# 1004.net
KiCad netlist of a schematic drawn in Altium Designer
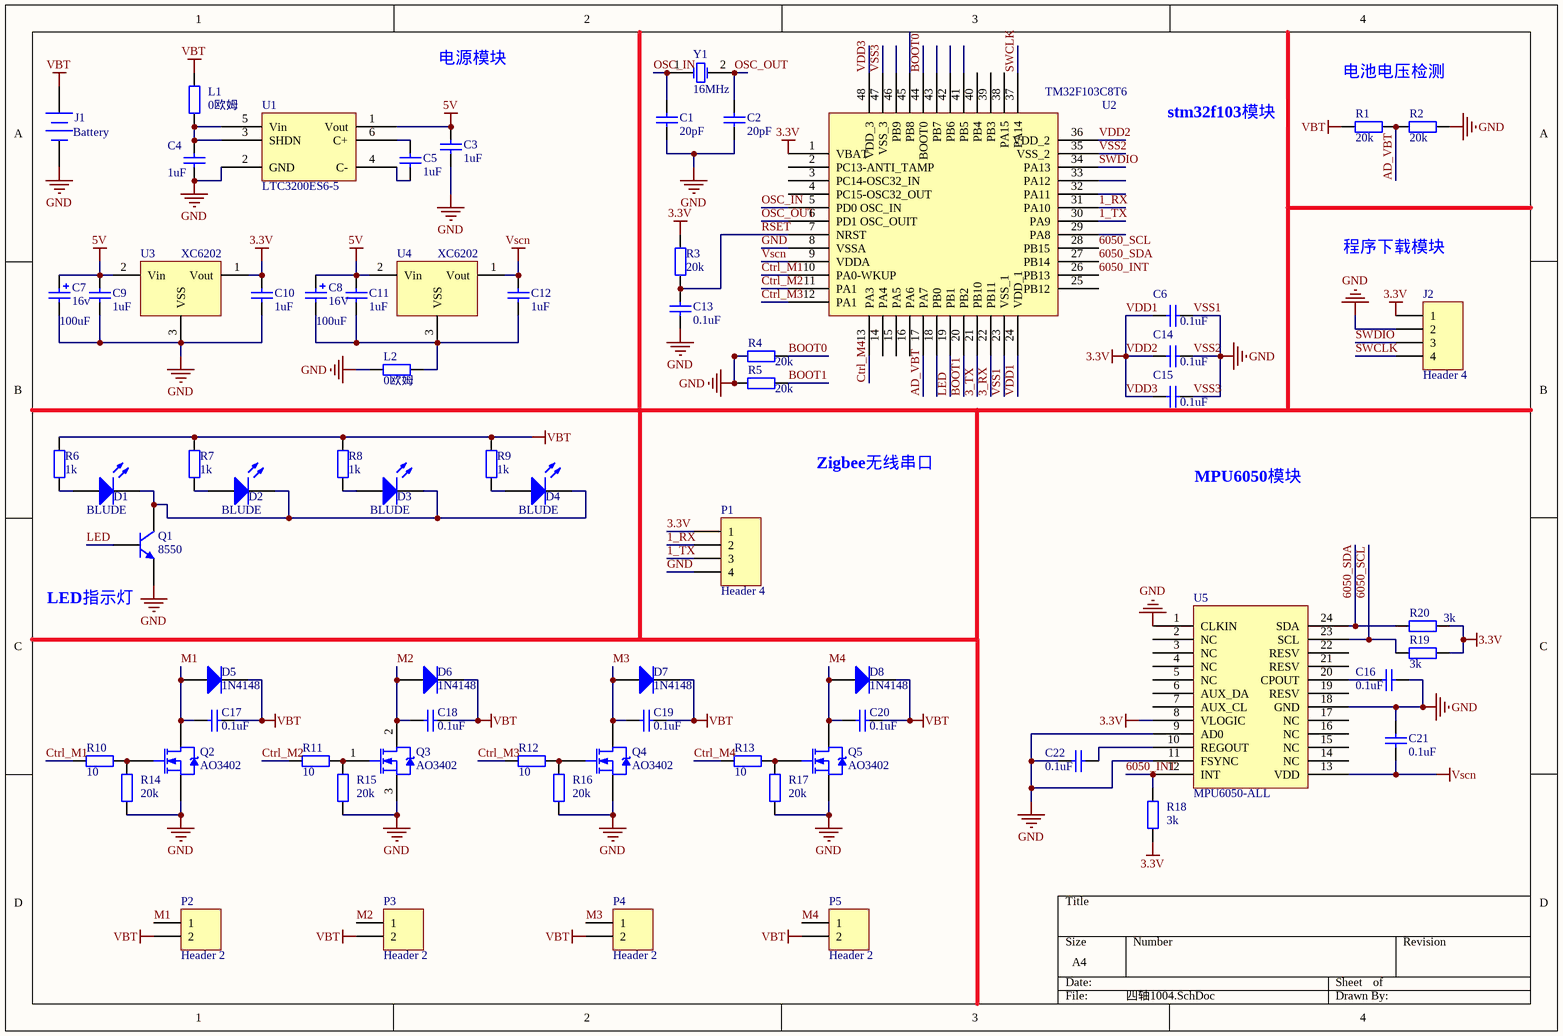
[diagram p0: 四轴1004.SchDoc]

(export (version "E")
  (design (tool "Eeschema 10.0.6"))
  (components
    (comp (ref "C1")
      (value "20pF")
      (footprint "J1-0603")
      (description "Capacitor")
      (fields (field (name "Comment") "Cap") (field (name "PUBLISHER") "Altium Limited"))
      (libsource (lib "Miscellaneous Devices") (part "Cap"))
    )
    (comp (ref "C2")
      (value "20pF")
      (footprint "J1-0603")
      (description "Capacitor")
      (fields (field (name "Comment") "Cap") (field (name "PUBLISHER") "Altium Limited"))
      (libsource (lib "Miscellaneous Devices") (part "Cap"))
    )
    (comp (ref "C3")
      (value "1uF")
      (footprint "J1-0603")
      (description "Capacitor")
      (fields (field (name "Comment") "Cap") (field (name "PUBLISHER") "Altium Limited"))
      (libsource (lib "Miscellaneous Devices") (part "Cap"))
    )
    (comp (ref "C4")
      (value "1uF")
      (footprint "J1-0603")
      (description "Capacitor")
      (fields (field (name "Comment") "Cap") (field (name "PUBLISHER") "Altium Limited"))
      (libsource (lib "Miscellaneous Devices") (part "Cap"))
    )
    (comp (ref "C5")
      (value "1uF")
      (footprint "J1-0603")
      (description "Capacitor")
      (fields (field (name "Comment") "Cap") (field (name "PUBLISHER") "Altium Limited"))
      (libsource (lib "Miscellaneous Devices") (part "Cap"))
    )
    (comp (ref "C6")
      (value "0.1uF")
      (footprint "J1-0603")
      (description "Capacitor")
      (fields (field (name "Comment") "Cap") (field (name "PUBLISHER") "Altium Limited"))
      (libsource (lib "Miscellaneous Devices") (part "Cap"))
    )
    (comp (ref "C7")
      (value "16v")
      (footprint "6032")
      (description "Polarized Capacitor (Axial)")
      (fields (field (name "ALTIUM_VALUE") "100uF") (field (name "PUBLISHER") "Altium Limited"))
      (libsource (lib "Miscellaneous Devices") (part "Cap Pol2"))
    )
    (comp (ref "C8")
      (value "16V")
      (footprint "6032")
      (description "Polarized Capacitor (Axial)")
      (fields (field (name "ALTIUM_VALUE") "100uF") (field (name "PUBLISHER") "Altium Limited"))
      (libsource (lib "Miscellaneous Devices") (part "Cap Pol2"))
    )
    (comp (ref "C9")
      (value "1uF")
      (footprint "J1-0603")
      (description "Capacitor")
      (fields (field (name "Comment") "Cap") (field (name "PUBLISHER") "Altium Limited"))
      (libsource (lib "Miscellaneous Devices") (part "Cap"))
    )
    (comp (ref "C10")
      (value "1uF")
      (footprint "J1-0603")
      (description "Capacitor")
      (fields (field (name "Comment") "Cap") (field (name "PUBLISHER") "Altium Limited"))
      (libsource (lib "Miscellaneous Devices") (part "Cap"))
    )
    (comp (ref "C11")
      (value "1uF")
      (footprint "J1-0603")
      (description "Capacitor")
      (fields (field (name "Comment") "Cap") (field (name "PUBLISHER") "Altium Limited"))
      (libsource (lib "Miscellaneous Devices") (part "Cap"))
    )
    (comp (ref "C12")
      (value "1uF")
      (footprint "J1-0603")
      (description "Capacitor")
      (fields (field (name "Comment") "Cap") (field (name "PUBLISHER") "Altium Limited"))
      (libsource (lib "Miscellaneous Devices") (part "Cap"))
    )
    (comp (ref "C13")
      (value "0.1uF")
      (footprint "J1-0603")
      (description "Capacitor")
      (fields (field (name "Comment") "Cap") (field (name "PUBLISHER") "Altium Limited"))
      (libsource (lib "Miscellaneous Devices") (part "Cap"))
    )
    (comp (ref "C14")
      (value "0.1uF")
      (footprint "J1-0603")
      (description "Capacitor")
      (fields (field (name "Comment") "Cap") (field (name "PUBLISHER") "Altium Limited"))
      (libsource (lib "Miscellaneous Devices") (part "Cap"))
    )
    (comp (ref "C15")
      (value "0.1uF")
      (footprint "J1-0603")
      (description "Capacitor")
      (fields (field (name "Comment") "Cap") (field (name "PUBLISHER") "Altium Limited"))
      (libsource (lib "Miscellaneous Devices") (part "Cap"))
    )
    (comp (ref "C16")
      (value "0.1uF")
      (footprint "J1-0603")
      (description "Capacitor")
      (fields (field (name "Comment") "Cap") (field (name "PUBLISHER") "Altium Limited"))
      (libsource (lib "Miscellaneous Devices") (part "Cap"))
    )
    (comp (ref "C17")
      (value "0.1uF")
      (footprint "J1-0603")
      (description "Capacitor")
      (fields (field (name "Comment") "Cap") (field (name "PUBLISHER") "Altium Limited"))
      (libsource (lib "Miscellaneous Devices") (part "Cap"))
    )
    (comp (ref "C18")
      (value "0.1uF")
      (footprint "J1-0603")
      (description "Capacitor")
      (fields (field (name "Comment") "Cap") (field (name "PUBLISHER") "Altium Limited"))
      (libsource (lib "Miscellaneous Devices") (part "Cap"))
    )
    (comp (ref "C19")
      (value "0.1uF")
      (footprint "J1-0603")
      (description "Capacitor")
      (fields (field (name "Comment") "Cap") (field (name "PUBLISHER") "Altium Limited"))
      (libsource (lib "Miscellaneous Devices") (part "Cap"))
    )
    (comp (ref "C20")
      (value "0.1uF")
      (footprint "J1-0603")
      (description "Capacitor")
      (fields (field (name "Comment") "Cap") (field (name "PUBLISHER") "Altium Limited"))
      (libsource (lib "Miscellaneous Devices") (part "Cap"))
    )
    (comp (ref "C21")
      (value "0.1uF")
      (footprint "J1-0603")
      (description "Capacitor")
      (fields (field (name "Comment") "Cap") (field (name "PUBLISHER") "Altium Limited"))
      (libsource (lib "Miscellaneous Devices") (part "Cap"))
    )
    (comp (ref "C22")
      (value "0.1uF")
      (footprint "J1-0603")
      (description "Capacitor")
      (fields (field (name "Comment") "Cap") (field (name "PUBLISHER") "Altium Limited"))
      (libsource (lib "Miscellaneous Devices") (part "Cap"))
    )
    (comp (ref "D1")
      (value "BLUDE")
      (footprint "J1-0603")
      (description "Typical INFRARED GaAs LED")
      (fields (field (name "PUBLISHER") "Altium Limited"))
      (libsource (lib "Miscellaneous Devices") (part "LED0"))
    )
    (comp (ref "D2")
      (value "BLUDE")
      (footprint "J1-0603")
      (description "Typical INFRARED GaAs LED")
      (fields (field (name "PUBLISHER") "Altium Limited"))
      (libsource (lib "Miscellaneous Devices") (part "LED0"))
    )
    (comp (ref "D3")
      (value "BLUDE")
      (footprint "J1-0603")
      (description "Typical INFRARED GaAs LED")
      (fields (field (name "PUBLISHER") "Altium Limited"))
      (libsource (lib "Miscellaneous Devices") (part "LED0"))
    )
    (comp (ref "D4")
      (value "BLUDE")
      (footprint "J1-0603")
      (description "Typical INFRARED GaAs LED")
      (fields (field (name "PUBLISHER") "Altium Limited"))
      (libsource (lib "Miscellaneous Devices") (part "LED0"))
    )
    (comp (ref "D5")
      (value "1N4148")
      (footprint "1206")
      (description "High Conductance Fast Diode")
      (fields (field (name "PUBLISHER") "Altium Limited"))
      (libsource (lib "Miscellaneous Devices") (part "Diode 1N4148"))
    )
    (comp (ref "D6")
      (value "1N4148")
      (footprint "1206")
      (description "High Conductance Fast Diode")
      (fields (field (name "PUBLISHER") "Altium Limited"))
      (libsource (lib "Miscellaneous Devices") (part "Diode 1N4148"))
    )
    (comp (ref "D7")
      (value "1N4148")
      (footprint "1206")
      (description "High Conductance Fast Diode")
      (fields (field (name "PUBLISHER") "Altium Limited"))
      (libsource (lib "Miscellaneous Devices") (part "Diode 1N4148"))
    )
    (comp (ref "D8")
      (value "1N4148")
      (footprint "1206")
      (description "High Conductance Fast Diode")
      (fields (field (name "PUBLISHER") "Altium Limited"))
      (libsource (lib "Miscellaneous Devices") (part "Diode 1N4148"))
    )
    (comp (ref "J1")
      (value "Battery")
      (footprint "DIP2-5.08")
      (description "Multicell Battery")
      (fields (field (name "PUBLISHER") "Altium Limited"))
      (libsource (lib "Miscellaneous Devices") (part "Battery"))
    )
    (comp (ref "J2")
      (value "Header 4")
      (footprint "HDR1X4")
      (description "Header, 4-Pin")
      (fields (field (name "PUBLISHER") "Altium Limited"))
      (libsource (lib "Miscellaneous Connectors") (part "Header 4"))
    )
    (comp (ref "L1")
      (value "0欧姆")
      (footprint "0805-1")
      (description "贴片电阻")
      (fields (field (name "Comment") "Res1") (field (name "PUBLISHER") "Altium Limited"))
      (libsource (lib "") (part "Res1_1"))
    )
    (comp (ref "L2")
      (value "0欧姆")
      (footprint "0805-1")
      (description "贴片电阻")
      (fields (field (name "Comment") "Res1") (field (name "PUBLISHER") "Altium Limited"))
      (libsource (lib "cell_1") (part "Res1"))
    )
    (comp (ref "P1")
      (value "Header 4")
      (footprint "HDR1X4")
      (description "Header, 4-Pin")
      (fields (field (name "PUBLISHER") "Altium Limited"))
      (libsource (lib "Miscellaneous Connectors") (part "Header 4"))
    )
    (comp (ref "P2")
      (value "Header 2")
      (footprint "DIP2-1.25")
      (description "Header, 2-Pin")
      (fields (field (name "PUBLISHER") "Altium Limited"))
      (libsource (lib "Miscellaneous Connectors") (part "Header 2"))
    )
    (comp (ref "P3")
      (value "Header 2")
      (footprint "DIP2-1.25")
      (description "Header, 2-Pin")
      (fields (field (name "PUBLISHER") "Altium Limited"))
      (libsource (lib "Miscellaneous Connectors") (part "Header 2"))
    )
    (comp (ref "P4")
      (value "Header 2")
      (footprint "DIP2-1.25")
      (description "Header, 2-Pin")
      (fields (field (name "PUBLISHER") "Altium Limited"))
      (libsource (lib "Miscellaneous Connectors") (part "Header 2"))
    )
    (comp (ref "P5")
      (value "Header 2")
      (footprint "DIP2-1.25")
      (description "Header, 2-Pin")
      (fields (field (name "PUBLISHER") "Altium Limited"))
      (libsource (lib "Miscellaneous Connectors") (part "Header 2"))
    )
    (comp (ref "Q1")
      (value "8550")
      (footprint "SOT23-8550")
      (description "NPN Bipolar Transistor")
      (fields (field (name "PUBLISHER") "Altium Limited"))
      (libsource (lib "Miscellaneous Devices") (part "QNPN"))
    )
    (comp (ref "Q2")
      (value "AO3402")
      (footprint "SOT-23")
      (description "N-Channel Power MOSFET")
      (fields (field (name "PUBLISHER") "Altium Limited"))
      (libsource (lib "") (part "NMOS-2_1"))
    )
    (comp (ref "Q3")
      (value "AO3402")
      (footprint "SOT-23")
      (description "N-Channel Power MOSFET")
      (fields (field (name "PUBLISHER") "Altium Limited"))
      (libsource (lib "Miscellaneous Devices") (part "NMOS-2"))
    )
    (comp (ref "Q4")
      (value "AO3402")
      (footprint "SOT-23")
      (description "N-Channel Power MOSFET")
      (fields (field (name "PUBLISHER") "Altium Limited"))
      (libsource (lib "") (part "NMOS-2_1"))
    )
    (comp (ref "Q5")
      (value "AO3402")
      (footprint "SOT-23")
      (description "N-Channel Power MOSFET")
      (fields (field (name "PUBLISHER") "Altium Limited"))
      (libsource (lib "") (part "NMOS-2_1"))
    )
    (comp (ref "R1")
      (value "20k")
      (footprint "J1-0603")
      (description "贴片电阻")
      (fields (field (name "Comment") "Res1") (field (name "PUBLISHER") "Altium Limited"))
      (libsource (lib "cell_1") (part "Res1"))
    )
    (comp (ref "R2")
      (value "20k")
      (footprint "J1-0603")
      (description "贴片电阻")
      (fields (field (name "Comment") "Res1") (field (name "PUBLISHER") "Altium Limited"))
      (libsource (lib "cell_1") (part "Res1"))
    )
    (comp (ref "R3")
      (value "20k")
      (footprint "J1-0603")
      (description "贴片电阻")
      (fields (field (name "Comment") "Res1") (field (name "PUBLISHER") "Altium Limited"))
      (libsource (lib "") (part "Res1_3"))
    )
    (comp (ref "R4")
      (value "20k")
      (footprint "J1-0603")
      (description "贴片电阻")
      (fields (field (name "Comment") "Res1") (field (name "PUBLISHER") "Altium Limited"))
      (libsource (lib "") (part "Res1_2"))
    )
    (comp (ref "R5")
      (value "20k")
      (footprint "J1-0603")
      (description "贴片电阻")
      (fields (field (name "Comment") "Res1") (field (name "PUBLISHER") "Altium Limited"))
      (libsource (lib "") (part "Res1_2"))
    )
    (comp (ref "R6")
      (value "1k")
      (footprint "J1-0603")
      (description "贴片电阻")
      (fields (field (name "Comment") "Res1") (field (name "PUBLISHER") "Altium Limited"))
      (libsource (lib "") (part "Res1_1"))
    )
    (comp (ref "R7")
      (value "1k")
      (footprint "J1-0603")
      (description "贴片电阻")
      (fields (field (name "Comment") "Res1") (field (name "PUBLISHER") "Altium Limited"))
      (libsource (lib "") (part "Res1_1"))
    )
    (comp (ref "R8")
      (value "1k")
      (footprint "J1-0603")
      (description "贴片电阻")
      (fields (field (name "Comment") "Res1") (field (name "PUBLISHER") "Altium Limited"))
      (libsource (lib "") (part "Res1_1"))
    )
    (comp (ref "R9")
      (value "1k")
      (footprint "J1-0603")
      (description "贴片电阻")
      (fields (field (name "Comment") "Res1") (field (name "PUBLISHER") "Altium Limited"))
      (libsource (lib "") (part "Res1_1"))
    )
    (comp (ref "R10")
      (value "10")
      (footprint "J1-0603")
      (description "贴片电阻")
      (fields (field (name "Comment") "Res1") (field (name "PUBLISHER") "Altium Limited"))
      (libsource (lib "cell_1") (part "Res1"))
    )
    (comp (ref "R11")
      (value "10")
      (footprint "J1-0603")
      (description "贴片电阻")
      (fields (field (name "Comment") "Res1") (field (name "PUBLISHER") "Altium Limited"))
      (libsource (lib "cell_1") (part "Res1"))
    )
    (comp (ref "R12")
      (value "10")
      (footprint "J1-0603")
      (description "贴片电阻")
      (fields (field (name "Comment") "Res1") (field (name "PUBLISHER") "Altium Limited"))
      (libsource (lib "cell_1") (part "Res1"))
    )
    (comp (ref "R13")
      (value "10")
      (footprint "J1-0603")
      (description "贴片电阻")
      (fields (field (name "Comment") "Res1") (field (name "PUBLISHER") "Altium Limited"))
      (libsource (lib "cell_1") (part "Res1"))
    )
    (comp (ref "R14")
      (value "20k")
      (footprint "J1-0603")
      (description "贴片电阻")
      (fields (field (name "Comment") "Res1") (field (name "PUBLISHER") "Altium Limited"))
      (libsource (lib "") (part "Res1_1"))
    )
    (comp (ref "R15")
      (value "20k")
      (footprint "J1-0603")
      (description "贴片电阻")
      (fields (field (name "Comment") "Res1") (field (name "PUBLISHER") "Altium Limited"))
      (libsource (lib "") (part "Res1_1"))
    )
    (comp (ref "R16")
      (value "20k")
      (footprint "J1-0603")
      (description "贴片电阻")
      (fields (field (name "Comment") "Res1") (field (name "PUBLISHER") "Altium Limited"))
      (libsource (lib "") (part "Res1_1"))
    )
    (comp (ref "R17")
      (value "20k")
      (footprint "J1-0603")
      (description "贴片电阻")
      (fields (field (name "Comment") "Res1") (field (name "PUBLISHER") "Altium Limited"))
      (libsource (lib "") (part "Res1_1"))
    )
    (comp (ref "R18")
      (value "3k")
      (footprint "J1-0603")
      (description "贴片电阻")
      (fields (field (name "Comment") "Res1") (field (name "PUBLISHER") "Altium Limited"))
      (libsource (lib "") (part "Res1_1"))
    )
    (comp (ref "R19")
      (value "3k")
      (footprint "J1-0603")
      (description "贴片电阻")
      (fields (field (name "Comment") "Res1") (field (name "PUBLISHER") "Altium Limited"))
      (libsource (lib "cell_1") (part "Res1"))
    )
    (comp (ref "R20")
      (value "3k")
      (footprint "J1-0603")
      (description "贴片电阻")
      (fields (field (name "Comment") "Res1") (field (name "PUBLISHER") "Altium Limited"))
      (libsource (lib "cell_1") (part "Res1"))
    )
    (comp (ref "U1")
      (value "LTC3200ES6-5")
      (footprint "SOT95P245X110-6N")
      (libsource (lib "NANSchlib1") (part "LTC3200ES6-5"))
    )
    (comp (ref "U2")
      (value "TM32F103C8T6")
      (footprint "LQFP48")
      (libsource (lib "NANSchlib1") (part "LQFP48-STM32F103C8T6"))
    )
    (comp (ref "U3") (value "XC6202") (footprint "SOT-23-NO") (libsource (lib "NANSchlib1") (part "XC6202")))
    (comp (ref "U4") (value "XC6202") (footprint "SOT-23-NO") (libsource (lib "NANSchlib1") (part "XC6202")))
    (comp (ref "U5")
      (value "MPU6050-ALL")
      (footprint "QFN50P440X440X80-24N")
      (libsource (lib "NANSchlib1") (part "MPU6050-ALL"))
    )
    (comp (ref "Y1")
      (value "16MHz")
      (footprint "3225--crystal")
      (description "Crystal Oscillator")
      (fields (field (name "PUBLISHER") "Altium Limited"))
      (libsource (lib "cell_1") (part "XTAL"))
    )
  )
  (nets
    (net (code "1") (name "/1_RX") (class "Default")
      (node (ref "P1") (pin "2") (pinfunction "2_2") (pintype "passive"))
      (node (ref "U2") (pin "31") (pinfunction "PA10_31") (pintype "passive"))
    )
    (net (code "2") (name "/1_TX") (class "Default")
      (node (ref "P1") (pin "3") (pinfunction "3_3") (pintype "passive"))
      (node (ref "U2") (pin "30") (pinfunction "PA9_30") (pintype "passive"))
    )
    (net (code "3") (name "/3_RX") (class "Default")
      (node (ref "U2") (pin "22") (pinfunction "PB11_22") (pintype "passive"))
    )
    (net (code "4") (name "/3_TX") (class "Default")
      (node (ref "U2") (pin "21") (pinfunction "PB10_21") (pintype "passive"))
    )
    (net (code "5") (name "/6050_INT") (class "Default")
      (node (ref "R18") (pin "2") (pinfunction "2_2") (pintype "passive"))
      (node (ref "U2") (pin "26") (pinfunction "PB13_26") (pintype "passive"))
      (node (ref "U5") (pin "12") (pinfunction "INT_12") (pintype "passive"))
    )
    (net (code "6") (name "/6050_SCL") (class "Default")
      (node (ref "R19") (pin "2") (pinfunction "2_2") (pintype "passive"))
      (node (ref "U2") (pin "28") (pinfunction "PB15_28") (pintype "passive"))
      (node (ref "U5") (pin "23") (pinfunction "SCL_23") (pintype "passive"))
    )
    (net (code "7") (name "/6050_SDA") (class "Default")
      (node (ref "R20") (pin "2") (pinfunction "2_2") (pintype "passive"))
      (node (ref "U2") (pin "27") (pinfunction "PB14_27") (pintype "passive"))
      (node (ref "U5") (pin "24") (pinfunction "SDA_24") (pintype "passive"))
    )
    (net (code "8") (name "/AD_VBT") (class "Default")
      (node (ref "R1") (pin "1") (pinfunction "1_1") (pintype "passive"))
      (node (ref "R2") (pin "2") (pinfunction "2_2") (pintype "passive"))
      (node (ref "U2") (pin "17") (pinfunction "PA7_17") (pintype "passive"))
    )
    (net (code "9") (name "/BOOT0") (class "Default")
      (node (ref "R4") (pin "2") (pinfunction "2_2") (pintype "passive"))
      (node (ref "U2") (pin "44") (pinfunction "BOOT0_44") (pintype "passive"))
    )
    (net (code "10") (name "/BOOT1") (class "Default")
      (node (ref "R5") (pin "2") (pinfunction "2_2") (pintype "passive"))
      (node (ref "U2") (pin "20") (pinfunction "PB2_20") (pintype "passive"))
    )
    (net (code "11") (name "/Ctrl_M1") (class "Default")
      (node (ref "R10") (pin "2") (pinfunction "2_2") (pintype "passive"))
      (node (ref "U2") (pin "10") (pinfunction "PA0-WKUP_10") (pintype "passive"))
    )
    (net (code "12") (name "/Ctrl_M2") (class "Default")
      (node (ref "R11") (pin "2") (pinfunction "2_2") (pintype "passive"))
      (node (ref "U2") (pin "11") (pinfunction "PA1_11") (pintype "passive"))
    )
    (net (code "13") (name "/Ctrl_M3") (class "Default")
      (node (ref "R12") (pin "2") (pinfunction "2_2") (pintype "passive"))
      (node (ref "U2") (pin "12") (pinfunction "PA1_12") (pintype "passive"))
    )
    (net (code "14") (name "/Ctrl_M4") (class "Default")
      (node (ref "R13") (pin "2") (pinfunction "2_2") (pintype "passive"))
      (node (ref "U2") (pin "13") (pinfunction "PA3_13") (pintype "passive"))
    )
    (net (code "15") (name "/LED") (class "Default")
      (node (ref "Q1") (pin "2") (pinfunction "B_2") (pintype "passive"))
      (node (ref "U2") (pin "19") (pinfunction "PB1_19") (pintype "passive"))
    )
    (net (code "16") (name "/M1") (class "Default")
      (node (ref "C17") (pin "1") (pinfunction "1_1") (pintype "passive"))
      (node (ref "D5") (pin "1") (pinfunction "A_1") (pintype "passive"))
      (node (ref "P2") (pin "1") (pinfunction "1_1") (pintype "passive"))
      (node (ref "Q2") (pin "2") (pinfunction "D_2") (pintype "passive"))
    )
    (net (code "17") (name "/M2") (class "Default")
      (node (ref "C18") (pin "1") (pinfunction "1_1") (pintype "passive"))
      (node (ref "D6") (pin "1") (pinfunction "A_1") (pintype "passive"))
      (node (ref "P3") (pin "1") (pinfunction "1_1") (pintype "passive"))
      (node (ref "Q3") (pin "2") (pinfunction "D_2") (pintype "passive"))
    )
    (net (code "18") (name "/M3") (class "Default")
      (node (ref "C19") (pin "1") (pinfunction "1_1") (pintype "passive"))
      (node (ref "D7") (pin "1") (pinfunction "A_1") (pintype "passive"))
      (node (ref "P4") (pin "1") (pinfunction "1_1") (pintype "passive"))
      (node (ref "Q4") (pin "2") (pinfunction "D_2") (pintype "passive"))
    )
    (net (code "19") (name "/M4") (class "Default")
      (node (ref "C20") (pin "1") (pinfunction "1_1") (pintype "passive"))
      (node (ref "D8") (pin "1") (pinfunction "A_1") (pintype "passive"))
      (node (ref "P5") (pin "1") (pinfunction "1_1") (pintype "passive"))
      (node (ref "Q5") (pin "2") (pinfunction "D_2") (pintype "passive"))
    )
    (net (code "20") (name "/OSC_IN") (class "Default")
      (node (ref "C1") (pin "2") (pinfunction "2_2") (pintype "passive"))
      (node (ref "U2") (pin "5") (pinfunction "PD0_OSC_IN_5") (pintype "passive"))
      (node (ref "Y1") (pin "1") (pinfunction "OSC1_1") (pintype "passive"))
    )
    (net (code "21") (name "/OSC_OUT") (class "Default")
      (node (ref "C2") (pin "2") (pinfunction "2_2") (pintype "passive"))
      (node (ref "U2") (pin "6") (pinfunction "PD1_OSC_OUIT_6") (pintype "passive"))
      (node (ref "Y1") (pin "2") (pinfunction "OSC2_2") (pintype "passive"))
    )
    (net (code "22") (name "/RSET") (class "Default")
      (node (ref "C13") (pin "1") (pinfunction "1_1") (pintype "passive"))
      (node (ref "R3") (pin "2") (pinfunction "2_2") (pintype "passive"))
      (node (ref "U2") (pin "7") (pinfunction "NRST_7") (pintype "passive"))
    )
    (net (code "23") (name "/SWCLK") (class "Default")
      (node (ref "J2") (pin "4") (pinfunction "4_4") (pintype "passive"))
      (node (ref "U2") (pin "37") (pinfunction "PA14_37") (pintype "passive"))
    )
    (net (code "24") (name "/SWDIO") (class "Default")
      (node (ref "J2") (pin "3") (pinfunction "3_3") (pintype "passive"))
      (node (ref "U2") (pin "34") (pinfunction "PA13_34") (pintype "passive"))
    )
    (net (code "25") (name "3.3V") (class "Default")
      (node (ref "C10") (pin "2") (pinfunction "2_2") (pintype "passive"))
      (node (ref "C14") (pin "2") (pinfunction "2_2") (pintype "passive"))
      (node (ref "C15") (pin "2") (pinfunction "2_2") (pintype "passive"))
      (node (ref "C6") (pin "2") (pinfunction "2_2") (pintype "passive"))
      (node (ref "J2") (pin "1") (pinfunction "1_1") (pintype "passive"))
      (node (ref "P1") (pin "1") (pinfunction "1_1") (pintype "passive"))
      (node (ref "R18") (pin "1") (pinfunction "1_1") (pintype "passive"))
      (node (ref "R19") (pin "1") (pinfunction "1_1") (pintype "passive"))
      (node (ref "R20") (pin "1") (pinfunction "1_1") (pintype "passive"))
      (node (ref "R3") (pin "1") (pinfunction "1_1") (pintype "passive"))
      (node (ref "U2") (pin "1") (pinfunction "VBAT_1") (pintype "passive"))
      (node (ref "U2") (pin "24") (pinfunction "VDD_1_24") (pintype "passive"))
      (node (ref "U2") (pin "36") (pinfunction "VDD_2_36") (pintype "passive"))
      (node (ref "U2") (pin "48") (pinfunction "VDD_3_48") (pintype "passive"))
      (node (ref "U3") (pin "1") (pinfunction "Vout_1") (pintype "passive"))
      (node (ref "U5") (pin "8") (pinfunction "VLOGIC_8") (pintype "passive"))
    )
    (net (code "26") (name "5V") (class "Default")
      (node (ref "C11") (pin "2") (pinfunction "2_2") (pintype "passive"))
      (node (ref "C3") (pin "2") (pinfunction "2_2") (pintype "passive"))
      (node (ref "C7") (pin "1") (pinfunction "1_1") (pintype "passive"))
      (node (ref "C8") (pin "1") (pinfunction "1_1") (pintype "passive"))
      (node (ref "C9") (pin "2") (pinfunction "2_2") (pintype "passive"))
      (node (ref "U1") (pin "1") (pinfunction "Vout_1") (pintype "passive"))
      (node (ref "U3") (pin "2") (pinfunction "Vin_2") (pintype "passive"))
      (node (ref "U4") (pin "2") (pinfunction "Vin_2") (pintype "passive"))
    )
    (net (code "27") (name "GND") (class "Default")
      (node (ref "C1") (pin "1") (pinfunction "1_1") (pintype "passive"))
      (node (ref "C10") (pin "1") (pinfunction "1_1") (pintype "passive"))
      (node (ref "C13") (pin "2") (pinfunction "2_2") (pintype "passive"))
      (node (ref "C14") (pin "1") (pinfunction "1_1") (pintype "passive"))
      (node (ref "C15") (pin "1") (pinfunction "1_1") (pintype "passive"))
      (node (ref "C16") (pin "2") (pinfunction "2_2") (pintype "passive"))
      (node (ref "C2") (pin "1") (pinfunction "1_1") (pintype "passive"))
      (node (ref "C21") (pin "1") (pinfunction "1_1") (pintype "passive"))
      (node (ref "C22") (pin "2") (pinfunction "2_2") (pintype "passive"))
      (node (ref "C3") (pin "1") (pinfunction "1_1") (pintype "passive"))
      (node (ref "C4") (pin "1") (pinfunction "1_1") (pintype "passive"))
      (node (ref "C6") (pin "1") (pinfunction "1_1") (pintype "passive"))
      (node (ref "C7") (pin "2") (pinfunction "2_2") (pintype "passive"))
      (node (ref "C9") (pin "1") (pinfunction "1_1") (pintype "passive"))
      (node (ref "J1") (pin "2") (pinfunction "-_2") (pintype "passive"))
      (node (ref "J2") (pin "2") (pinfunction "2_2") (pintype "passive"))
      (node (ref "L2") (pin "2") (pinfunction "2_2") (pintype "passive"))
      (node (ref "P1") (pin "4") (pinfunction "4_4") (pintype "passive"))
      (node (ref "Q1") (pin "3") (pinfunction "E_3") (pintype "passive"))
      (node (ref "Q2") (pin "3") (pinfunction "S_3") (pintype "passive"))
      (node (ref "Q3") (pin "3") (pinfunction "S_3") (pintype "passive"))
      (node (ref "Q4") (pin "3") (pinfunction "S_3") (pintype "passive"))
      (node (ref "Q5") (pin "3") (pinfunction "S_3") (pintype "passive"))
      (node (ref "R14") (pin "1") (pinfunction "1_1") (pintype "passive"))
      (node (ref "R15") (pin "1") (pinfunction "1_1") (pintype "passive"))
      (node (ref "R16") (pin "1") (pinfunction "1_1") (pintype "passive"))
      (node (ref "R17") (pin "1") (pinfunction "1_1") (pintype "passive"))
      (node (ref "R2") (pin "1") (pinfunction "1_1") (pintype "passive"))
      (node (ref "R4") (pin "1") (pinfunction "1_1") (pintype "passive"))
      (node (ref "R5") (pin "1") (pinfunction "1_1") (pintype "passive"))
      (node (ref "U1") (pin "2") (pinfunction "GND_2") (pintype "passive"))
      (node (ref "U2") (pin "23") (pinfunction "VSS_1_23") (pintype "passive"))
      (node (ref "U2") (pin "35") (pinfunction "VSS_2_35") (pintype "passive"))
      (node (ref "U2") (pin "47") (pinfunction "VSS_3_47") (pintype "passive"))
      (node (ref "U2") (pin "8") (pinfunction "VSSA_8") (pintype "passive"))
      (node (ref "U3") (pin "3") (pinfunction "VSS_3") (pintype "passive"))
      (node (ref "U5") (pin "1") (pinfunction "CLKIN_1") (pintype "passive"))
      (node (ref "U5") (pin "11") (pinfunction "FSYNC_11") (pintype "passive"))
      (node (ref "U5") (pin "18") (pinfunction "GND_18") (pintype "passive"))
      (node (ref "U5") (pin "9") (pinfunction "AD0_9") (pintype "passive"))
    )
    (net (code "28") (name "Net-(D1-A)") (class "Default")
      (node (ref "D1") (pin "1") (pinfunction "A_1") (pintype "passive"))
      (node (ref "R6") (pin "1") (pinfunction "1_1") (pintype "passive"))
    )
    (net (code "29") (name "Net-(D1-K)") (class "Default")
      (node (ref "D1") (pin "2") (pinfunction "K_2") (pintype "passive"))
      (node (ref "D2") (pin "2") (pinfunction "K_2") (pintype "passive"))
      (node (ref "D3") (pin "2") (pinfunction "K_2") (pintype "passive"))
      (node (ref "D4") (pin "2") (pinfunction "K_2") (pintype "passive"))
      (node (ref "Q1") (pin "1") (pinfunction "C_1") (pintype "passive"))
    )
    (net (code "30") (name "Net-(D2-A)") (class "Default")
      (node (ref "D2") (pin "1") (pinfunction "A_1") (pintype "passive"))
      (node (ref "R7") (pin "1") (pinfunction "1_1") (pintype "passive"))
    )
    (net (code "31") (name "Net-(D3-A)") (class "Default")
      (node (ref "D3") (pin "1") (pinfunction "A_1") (pintype "passive"))
      (node (ref "R8") (pin "1") (pinfunction "1_1") (pintype "passive"))
    )
    (net (code "32") (name "Net-(D4-A)") (class "Default")
      (node (ref "D4") (pin "1") (pinfunction "A_1") (pintype "passive"))
      (node (ref "R9") (pin "1") (pinfunction "1_1") (pintype "passive"))
    )
    (net (code "33") (name "Net-(Q2-G)") (class "Default")
      (node (ref "Q2") (pin "1") (pinfunction "G_1") (pintype "passive"))
      (node (ref "R10") (pin "1") (pinfunction "1_1") (pintype "passive"))
      (node (ref "R14") (pin "2") (pinfunction "2_2") (pintype "passive"))
    )
    (net (code "34") (name "Net-(Q3-G)") (class "Default")
      (node (ref "Q3") (pin "1") (pinfunction "G_1") (pintype "passive"))
      (node (ref "R11") (pin "1") (pinfunction "1_1") (pintype "passive"))
      (node (ref "R15") (pin "2") (pinfunction "2_2") (pintype "passive"))
    )
    (net (code "35") (name "Net-(Q4-G)") (class "Default")
      (node (ref "Q4") (pin "1") (pinfunction "G_1") (pintype "passive"))
      (node (ref "R12") (pin "1") (pinfunction "1_1") (pintype "passive"))
      (node (ref "R16") (pin "2") (pinfunction "2_2") (pintype "passive"))
    )
    (net (code "36") (name "Net-(Q5-G)") (class "Default")
      (node (ref "Q5") (pin "1") (pinfunction "G_1") (pintype "passive"))
      (node (ref "R13") (pin "1") (pinfunction "1_1") (pintype "passive"))
      (node (ref "R17") (pin "2") (pinfunction "2_2") (pintype "passive"))
    )
    (net (code "37") (name "Net-(U1-C+)") (class "Default")
      (node (ref "C5") (pin "2") (pinfunction "2_2") (pintype "passive"))
      (node (ref "U1") (pin "6") (pinfunction "C+_6") (pintype "passive"))
    )
    (net (code "38") (name "Net-(U1-C-)") (class "Default")
      (node (ref "C5") (pin "1") (pinfunction "1_1") (pintype "passive"))
      (node (ref "U1") (pin "4") (pinfunction "C-_4") (pintype "passive"))
    )
    (net (code "39") (name "Net-(U1-SHDN)") (class "Default")
      (node (ref "C4") (pin "2") (pinfunction "2_2") (pintype "passive"))
      (node (ref "L1") (pin "1") (pinfunction "1_1") (pintype "passive"))
      (node (ref "U1") (pin "3") (pinfunction "SHDN_3") (pintype "passive"))
      (node (ref "U1") (pin "5") (pinfunction "Vin_5") (pintype "passive"))
    )
    (net (code "40") (name "Net-(U4-VSS)") (class "Default")
      (node (ref "C11") (pin "1") (pinfunction "1_1") (pintype "passive"))
      (node (ref "C12") (pin "1") (pinfunction "1_1") (pintype "passive"))
      (node (ref "C8") (pin "2") (pinfunction "2_2") (pintype "passive"))
      (node (ref "L2") (pin "1") (pinfunction "1_1") (pintype "passive"))
      (node (ref "U4") (pin "3") (pinfunction "VSS_3") (pintype "passive"))
    )
    (net (code "41") (name "Net-(U5-CPOUT)") (class "Default")
      (node (ref "C16") (pin "1") (pinfunction "1_1") (pintype "passive"))
      (node (ref "U5") (pin "20") (pinfunction "CPOUT_20") (pintype "passive"))
    )
    (net (code "42") (name "Net-(U5-REGOUT)") (class "Default")
      (node (ref "C22") (pin "1") (pinfunction "1_1") (pintype "passive"))
      (node (ref "U5") (pin "10") (pinfunction "REGOUT_10") (pintype "passive"))
    )
    (net (code "43") (name "VBT") (class "Default")
      (node (ref "C17") (pin "2") (pinfunction "2_2") (pintype "passive"))
      (node (ref "C18") (pin "2") (pinfunction "2_2") (pintype "passive"))
      (node (ref "C19") (pin "2") (pinfunction "2_2") (pintype "passive"))
      (node (ref "C20") (pin "2") (pinfunction "2_2") (pintype "passive"))
      (node (ref "D5") (pin "2") (pinfunction "K_2") (pintype "passive"))
      (node (ref "D6") (pin "2") (pinfunction "K_2") (pintype "passive"))
      (node (ref "D7") (pin "2") (pinfunction "K_2") (pintype "passive"))
      (node (ref "D8") (pin "2") (pinfunction "K_2") (pintype "passive"))
      (node (ref "J1") (pin "1") (pinfunction "+_1") (pintype "passive"))
      (node (ref "L1") (pin "2") (pinfunction "2_2") (pintype "passive"))
      (node (ref "P2") (pin "2") (pinfunction "2_2") (pintype "passive"))
      (node (ref "P3") (pin "2") (pinfunction "2_2") (pintype "passive"))
      (node (ref "P4") (pin "2") (pinfunction "2_2") (pintype "passive"))
      (node (ref "P5") (pin "2") (pinfunction "2_2") (pintype "passive"))
      (node (ref "R1") (pin "2") (pinfunction "2_2") (pintype "passive"))
      (node (ref "R6") (pin "2") (pinfunction "2_2") (pintype "passive"))
      (node (ref "R7") (pin "2") (pinfunction "2_2") (pintype "passive"))
      (node (ref "R8") (pin "2") (pinfunction "2_2") (pintype "passive"))
      (node (ref "R9") (pin "2") (pinfunction "2_2") (pintype "passive"))
    )
    (net (code "44") (name "Vscn") (class "Default")
      (node (ref "C12") (pin "2") (pinfunction "2_2") (pintype "passive"))
      (node (ref "C21") (pin "2") (pinfunction "2_2") (pintype "passive"))
      (node (ref "U2") (pin "9") (pinfunction "VDDA_9") (pintype "passive"))
      (node (ref "U4") (pin "1") (pinfunction "Vout_1") (pintype "passive"))
      (node (ref "U5") (pin "13") (pinfunction "VDD_13") (pintype "passive"))
    )
    (net (code "45") (name "unconnected-(U2-PA4-Pad14)") (class "Default")
      (node (ref "U2") (pin "14") (pinfunction "PA4_14") (pintype "passive"))
    )
    (net (code "46") (name "unconnected-(U2-PA5-Pad15)") (class "Default")
      (node (ref "U2") (pin "15") (pinfunction "PA5_15") (pintype "passive"))
    )
    (net (code "47") (name "unconnected-(U2-PA6-Pad16)") (class "Default")
      (node (ref "U2") (pin "16") (pinfunction "PA6_16") (pintype "passive"))
    )
    (net (code "48") (name "unconnected-(U2-PA8-Pad29)") (class "Default")
      (node (ref "U2") (pin "29") (pinfunction "PA8_29") (pintype "passive"))
    )
    (net (code "49") (name "unconnected-(U2-PA11-Pad32)") (class "Default")
      (node (ref "U2") (pin "32") (pinfunction "PA11_32") (pintype "passive"))
    )
    (net (code "50") (name "unconnected-(U2-PA12-Pad33)") (class "Default")
      (node (ref "U2") (pin "33") (pinfunction "PA12_33") (pintype "passive"))
    )
    (net (code "51") (name "unconnected-(U2-PA15-Pad38)") (class "Default")
      (node (ref "U2") (pin "38") (pinfunction "PA15_38") (pintype "passive"))
    )
    (net (code "52") (name "unconnected-(U2-PB0-Pad18)") (class "Default")
      (node (ref "U2") (pin "18") (pinfunction "PB0_18") (pintype "passive"))
    )
    (net (code "53") (name "unconnected-(U2-PB3-Pad39)") (class "Default")
      (node (ref "U2") (pin "39") (pinfunction "PB3_39") (pintype "passive"))
    )
    (net (code "54") (name "unconnected-(U2-PB4-Pad40)") (class "Default")
      (node (ref "U2") (pin "40") (pinfunction "PB4_40") (pintype "passive"))
    )
    (net (code "55") (name "unconnected-(U2-PB5-Pad41)") (class "Default")
      (node (ref "U2") (pin "41") (pinfunction "PB5_41") (pintype "passive"))
    )
    (net (code "56") (name "unconnected-(U2-PB6-Pad42)") (class "Default")
      (node (ref "U2") (pin "42") (pinfunction "PB6_42") (pintype "passive"))
    )
    (net (code "57") (name "unconnected-(U2-PB7-Pad43)") (class "Default")
      (node (ref "U2") (pin "43") (pinfunction "PB7_43") (pintype "passive"))
    )
    (net (code "58") (name "unconnected-(U2-PB8-Pad45)") (class "Default")
      (node (ref "U2") (pin "45") (pinfunction "PB8_45") (pintype "passive"))
    )
    (net (code "59") (name "unconnected-(U2-PB9-Pad46)") (class "Default")
      (node (ref "U2") (pin "46") (pinfunction "PB9_46") (pintype "passive"))
    )
    (net (code "60") (name "unconnected-(U2-PB12-Pad25)") (class "Default")
      (node (ref "U2") (pin "25") (pinfunction "PB12_25") (pintype "passive"))
    )
    (net (code "61") (name "unconnected-(U2-PC13-ANTI_TAMP-Pad2)") (class "Default")
      (node (ref "U2") (pin "2") (pinfunction "PC13-ANTI_TAMP_2") (pintype "passive"))
    )
    (net (code "62") (name "unconnected-(U2-PC14-OSC32_IN-Pad3)") (class "Default")
      (node (ref "U2") (pin "3") (pinfunction "PC14-OSC32_IN_3") (pintype "passive"))
    )
    (net (code "63") (name "unconnected-(U2-PC15-OSC32_OUT-Pad4)") (class "Default")
      (node (ref "U2") (pin "4") (pinfunction "PC15-OSC32_OUT_4") (pintype "passive"))
    )
    (net (code "64") (name "unconnected-(U5-AUX_CL-Pad7)") (class "Default")
      (node (ref "U5") (pin "7") (pinfunction "AUX_CL_7") (pintype "passive"))
    )
    (net (code "65") (name "unconnected-(U5-AUX_DA-Pad6)") (class "Default")
      (node (ref "U5") (pin "6") (pinfunction "AUX_DA_6") (pintype "passive"))
    )
    (net (code "66") (name "unconnected-(U5-NC-Pad2)") (class "Default")
      (node (ref "U5") (pin "2") (pinfunction "NC_2") (pintype "passive"))
    )
    (net (code "67") (name "unconnected-(U5-NC-Pad3)") (class "Default")
      (node (ref "U5") (pin "3") (pinfunction "NC_3") (pintype "passive"))
    )
    (net (code "68") (name "unconnected-(U5-NC-Pad4)") (class "Default")
      (node (ref "U5") (pin "4") (pinfunction "NC_4") (pintype "passive"))
    )
    (net (code "69") (name "unconnected-(U5-NC-Pad5)") (class "Default")
      (node (ref "U5") (pin "5") (pinfunction "NC_5") (pintype "passive"))
    )
    (net (code "70") (name "unconnected-(U5-NC-Pad14)") (class "Default")
      (node (ref "U5") (pin "14") (pinfunction "NC_14") (pintype "passive"))
    )
    (net (code "71") (name "unconnected-(U5-NC-Pad15)") (class "Default")
      (node (ref "U5") (pin "15") (pinfunction "NC_15") (pintype "passive"))
    )
    (net (code "72") (name "unconnected-(U5-NC-Pad16)") (class "Default")
      (node (ref "U5") (pin "16") (pinfunction "NC_16") (pintype "passive"))
    )
    (net (code "73") (name "unconnected-(U5-NC-Pad17)") (class "Default")
      (node (ref "U5") (pin "17") (pinfunction "NC_17") (pintype "passive"))
    )
    (net (code "74") (name "unconnected-(U5-RESV-Pad19)") (class "Default")
      (node (ref "U5") (pin "19") (pinfunction "RESV_19") (pintype "passive"))
    )
    (net (code "75") (name "unconnected-(U5-RESV-Pad21)") (class "Default")
      (node (ref "U5") (pin "21") (pinfunction "RESV_21") (pintype "passive"))
    )
    (net (code "76") (name "unconnected-(U5-RESV-Pad22)") (class "Default")
      (node (ref "U5") (pin "22") (pinfunction "RESV_22") (pintype "passive"))
    )
  )
)
